# Left.net
KiCad netlist of a schematic drawn in EAGLE
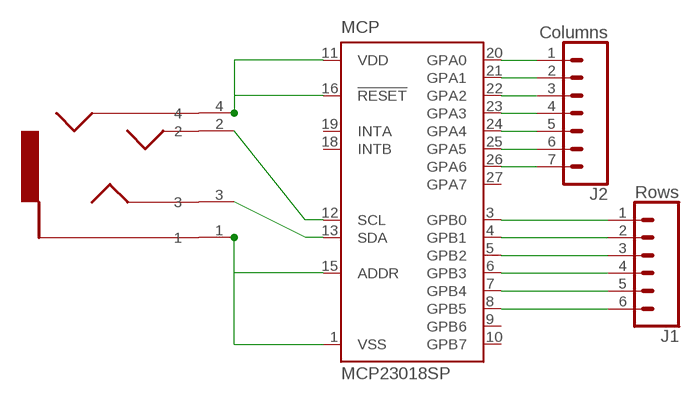
[diagram p0: schematic, sheet 1]

(export (version "E")
  (design (tool "Eeschema 10.0.6"))
  (components
    (comp (ref "J1")
      (value "Rows")
      (footprint "eagle-import:1X06")
      (libsource (lib "eagle-import") (part "CONN_06SILK_FEMALE_PTH"))
    )
    (comp (ref "J2")
      (value "Columns")
      (footprint "eagle-import:1X07")
      (libsource (lib "eagle-import") (part "CONN_07"))
    )
    (comp (ref "MCP")
      (value "MCP23018SP")
      (footprint "eagle-import:DIL28-3")
      (fields (field (name "MF") "MICROCHIP") (field (name "MPN") "MCP23018-E/SP"))
      (libsource (lib "eagle-import") (part "MCP23018SP"))
    )
    (comp (ref "U$1")
      (value "SJ-43514_HEADPHONES_3.5MM_X4")
      (footprint "eagle-import:SJ-43514_HEADPHONES-3.5MM_X4")
      (libsource (lib "eagle-import") (part "SJ-43514_HEADPHONES_3.5MM_X4"))
    )
  )
  (nets
    (net (code "1") (name "Net-(MCP-ADDR)") (class "Default")
      (node (ref "MCP") (pin "1") (pinfunction "VSS_1") (pintype "power_in"))
      (node (ref "MCP") (pin "15") (pinfunction "ADDR_15") (pintype "input"))
      (node (ref "U$1") (pin "1") (pinfunction "1_1") (pintype "bidirectional"))
    )
    (net (code "2") (name "Net-(MCP-GPA0)") (class "Default")
      (node (ref "J2") (pin "1") (pinfunction "1_1") (pintype "passive"))
      (node (ref "MCP") (pin "20") (pinfunction "GPA0_20") (pintype "bidirectional"))
    )
    (net (code "3") (name "Net-(MCP-GPA1)") (class "Default")
      (node (ref "J2") (pin "2") (pinfunction "2_2") (pintype "passive"))
      (node (ref "MCP") (pin "21") (pinfunction "GPA1_21") (pintype "bidirectional"))
    )
    (net (code "4") (name "Net-(MCP-GPA2)") (class "Default")
      (node (ref "J2") (pin "3") (pinfunction "3_3") (pintype "passive"))
      (node (ref "MCP") (pin "22") (pinfunction "GPA2_22") (pintype "bidirectional"))
    )
    (net (code "5") (name "Net-(MCP-GPA3)") (class "Default")
      (node (ref "J2") (pin "4") (pinfunction "4_4") (pintype "passive"))
      (node (ref "MCP") (pin "23") (pinfunction "GPA3_23") (pintype "bidirectional"))
    )
    (net (code "6") (name "Net-(MCP-GPA4)") (class "Default")
      (node (ref "J2") (pin "5") (pinfunction "5_5") (pintype "passive"))
      (node (ref "MCP") (pin "24") (pinfunction "GPA4_24") (pintype "bidirectional"))
    )
    (net (code "7") (name "Net-(MCP-GPA5)") (class "Default")
      (node (ref "J2") (pin "6") (pinfunction "6_6") (pintype "passive"))
      (node (ref "MCP") (pin "25") (pinfunction "GPA5_25") (pintype "bidirectional"))
    )
    (net (code "8") (name "Net-(MCP-GPA6)") (class "Default")
      (node (ref "J2") (pin "7") (pinfunction "7_7") (pintype "passive"))
      (node (ref "MCP") (pin "26") (pinfunction "GPA6_26") (pintype "bidirectional"))
    )
    (net (code "9") (name "Net-(MCP-GPB0)") (class "Default")
      (node (ref "J1") (pin "1") (pinfunction "1_1") (pintype "passive"))
      (node (ref "MCP") (pin "3") (pinfunction "GPB0_3") (pintype "bidirectional"))
    )
    (net (code "10") (name "Net-(MCP-GPB1)") (class "Default")
      (node (ref "J1") (pin "2") (pinfunction "2_2") (pintype "passive"))
      (node (ref "MCP") (pin "4") (pinfunction "GPB1_4") (pintype "bidirectional"))
    )
    (net (code "11") (name "Net-(MCP-GPB2)") (class "Default")
      (node (ref "J1") (pin "3") (pinfunction "3_3") (pintype "passive"))
      (node (ref "MCP") (pin "5") (pinfunction "GPB2_5") (pintype "bidirectional"))
    )
    (net (code "12") (name "Net-(MCP-GPB3)") (class "Default")
      (node (ref "J1") (pin "4") (pinfunction "4_4") (pintype "passive"))
      (node (ref "MCP") (pin "6") (pinfunction "GPB3_6") (pintype "bidirectional"))
    )
    (net (code "13") (name "Net-(MCP-GPB4)") (class "Default")
      (node (ref "J1") (pin "5") (pinfunction "5_5") (pintype "passive"))
      (node (ref "MCP") (pin "7") (pinfunction "GPB4_7") (pintype "bidirectional"))
    )
    (net (code "14") (name "Net-(MCP-GPB5)") (class "Default")
      (node (ref "J1") (pin "6") (pinfunction "6_6") (pintype "passive"))
      (node (ref "MCP") (pin "8") (pinfunction "GPB5_8") (pintype "bidirectional"))
    )
    (net (code "15") (name "Net-(MCP-SCL)") (class "Default")
      (node (ref "MCP") (pin "12") (pinfunction "SCL_12") (pintype "input"))
      (node (ref "U$1") (pin "2") (pinfunction "2_2") (pintype "bidirectional"))
    )
    (net (code "16") (name "Net-(MCP-SDA)") (class "Default")
      (node (ref "MCP") (pin "13") (pinfunction "SDA_13") (pintype "bidirectional"))
      (node (ref "U$1") (pin "3") (pinfunction "3_3") (pintype "bidirectional"))
    )
    (net (code "17") (name "Net-(MCP-VDD)") (class "Default")
      (node (ref "MCP") (pin "11") (pinfunction "VDD_11") (pintype "power_in"))
      (node (ref "MCP") (pin "16") (pinfunction "~{RESET}_16") (pintype "input"))
      (node (ref "U$1") (pin "4") (pinfunction "4_4") (pintype "bidirectional"))
    )
    (net (code "18") (name "unconnected-(MCP-GPA7-Pad27)") (class "Default")
      (node (ref "MCP") (pin "27") (pinfunction "GPA7_27") (pintype "bidirectional"))
    )
    (net (code "19") (name "unconnected-(MCP-GPB6-Pad9)") (class "Default")
      (node (ref "MCP") (pin "9") (pinfunction "GPB6_9") (pintype "bidirectional"))
    )
    (net (code "20") (name "unconnected-(MCP-GPB7-Pad10)") (class "Default")
      (node (ref "MCP") (pin "10") (pinfunction "GPB7_10") (pintype "bidirectional"))
    )
    (net (code "21") (name "unconnected-(MCP-INTA-Pad19)") (class "Default")
      (node (ref "MCP") (pin "19") (pinfunction "INTA_19") (pintype "output"))
    )
    (net (code "22") (name "unconnected-(MCP-INTB-Pad18)") (class "Default")
      (node (ref "MCP") (pin "18") (pinfunction "INTB_18") (pintype "output"))
    )
  )
)
